# power.net
KiCad netlist of a schematic drawn in Altium Designer
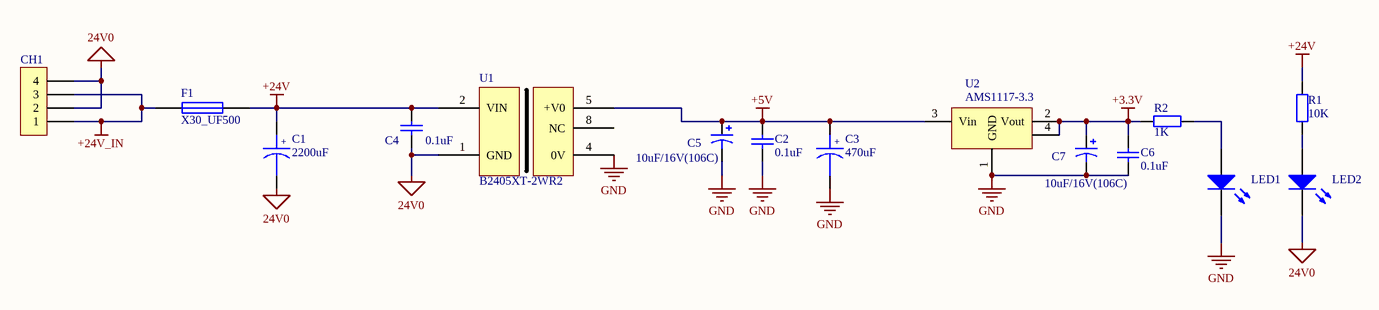
[diagram p0: power.SchDoc]

(export (version "E")
  (design (tool "Eeschema 10.0.6"))
  (components
    (comp (ref "C1")
      (value "C_2200uF")
      (footprint "C7.8*17")
      (fields (field (name "ALTIUM_UNNAMED_1") "2200uF"))
      (libsource (lib "myIntegrated_Library1") (part "C_2200uF"))
    )
    (comp (ref "C2")
      (value "0.1uF")
      (footprint "0805")
      (description "Capacitor")
      (fields (field (name "Comment") "Cap") (field (name "PUBLISHER") "Altium Limited"))
      (libsource (lib "Miscellaneous Devices") (part "Cap"))
    )
    (comp (ref "C3")
      (value "C_2200uF")
      (footprint "C5*10")
      (fields (field (name "ALTIUM_UNNAMED_1") "470uF"))
      (libsource (lib "myIntegrated_Library1") (part "C_2200uF"))
    )
    (comp (ref "C4")
      (value "0.1uF")
      (footprint "0805")
      (description "Capacitor")
      (fields (field (name "Comment") "Cap") (field (name "PUBLISHER") "Altium Limited"))
      (libsource (lib "Miscellaneous Devices") (part "Cap"))
    )
    (comp (ref "C5")
      (value "10uF/16V(106C)")
      (footprint "CAP A-3216")
      (description "Polarized Capacitor (Surface Mount)")
      (fields (field (name "Comment") "Cap Pol3") (field (name "PUBLISHER") "Altium Limited"))
      (libsource (lib "Miscellaneous Devices") (part "Cap Pol3"))
    )
    (comp (ref "C6")
      (value "0.1uF")
      (footprint "0805")
      (description "Capacitor")
      (fields (field (name "Comment") "Cap") (field (name "PUBLISHER") "Altium Limited"))
      (libsource (lib "Miscellaneous Devices") (part "Cap"))
    )
    (comp (ref "C7")
      (value "10uF/16V(106C)")
      (footprint "CAP A-3216")
      (description "Polarized Capacitor (Surface Mount)")
      (fields (field (name "Comment") "Cap Pol3") (field (name "PUBLISHER") "Altium Limited"))
      (libsource (lib "Miscellaneous Devices") (part "Cap Pol3"))
    )
    (comp (ref "CH1")
      (value "HEADER1X4")
      (footprint "CH3.96-4PIN")
      (libsource (lib "myIntegrated_Library1") (part "HEADER1X4"))
    )
    (comp (ref "F1")
      (value "X30_UF500")
      (footprint "X30UF600")
      (description "Fuse")
      (fields (field (name "PUBLISHER") "Altium Limited"))
      (libsource (lib "Miscellaneous Devices") (part "Fuse 1"))
    )
    (comp (ref "LED1")
      (value "~")
      (footprint "LED-0805")
      (description "Typical RED, GREEN, YELLOW, AMBER GaAs LED")
      (fields (field (name "PUBLISHER") "Altium Limited"))
      (libsource (lib "Miscellaneous Devices") (part "LED2"))
    )
    (comp (ref "LED2")
      (value "~")
      (footprint "LED-0805")
      (description "Typical RED, GREEN, YELLOW, AMBER GaAs LED")
      (fields (field (name "PUBLISHER") "Altium Limited"))
      (libsource (lib "Miscellaneous Devices") (part "LED2"))
    )
    (comp (ref "R1")
      (value "10K")
      (footprint "0805")
      (description "Resistor")
      (fields (field (name "Comment") "Res2") (field (name "PUBLISHER") "Altium Limited"))
      (libsource (lib "Miscellaneous Devices") (part "Res2"))
    )
    (comp (ref "R2")
      (value "1K")
      (footprint "0805")
      (description "Resistor")
      (fields (field (name "Comment") "Res2") (field (name "PUBLISHER") "Altium Limited"))
      (libsource (lib "") (part "Res2_1"))
    )
    (comp (ref "U1")
      (value "B2405XT-2WR2")
      (footprint "B2405XT-2WR2")
      (libsource (lib "myIntegrated_Library1") (part "B2405XT-2WR2"))
    )
    (comp (ref "U2")
      (value "AMS1117-3.3")
      (footprint "SOT223")
      (libsource (lib "货架电子标签元件库") (part "AMS1117-5"))
    )
  )
  (nets
    (net (code "1") (name "+3.3V") (class "Default")
      (node (ref "C6") (pin "2") (pinfunction "2_2") (pintype "passive"))
      (node (ref "C7") (pin "1") (pinfunction "1_1") (pintype "passive"))
      (node (ref "R2") (pin "2") (pinfunction "2_2") (pintype "passive"))
      (node (ref "U2") (pin "2") (pinfunction "Vout_2") (pintype "passive"))
      (node (ref "U2") (pin "4") (pintype "passive"))
    )
    (net (code "2") (name "+5V") (class "Default")
      (node (ref "C2") (pin "2") (pinfunction "2_2") (pintype "passive"))
      (node (ref "C3") (pin "1") (pinfunction "1_1") (pintype "passive"))
      (node (ref "C5") (pin "1") (pinfunction "1_1") (pintype "passive"))
      (node (ref "U1") (pin "5") (pinfunction "+V0_5") (pintype "passive"))
      (node (ref "U2") (pin "3") (pinfunction "Vin_3") (pintype "passive"))
    )
    (net (code "3") (name "+24V") (class "Default")
      (node (ref "C1") (pin "1") (pinfunction "1_1") (pintype "passive"))
      (node (ref "C4") (pin "2") (pinfunction "2_2") (pintype "passive"))
      (node (ref "F1") (pin "2") (pinfunction "2_2") (pintype "passive"))
      (node (ref "R1") (pin "2") (pinfunction "2_2") (pintype "passive"))
      (node (ref "U1") (pin "2") (pinfunction "VIN_2") (pintype "passive"))
    )
    (net (code "4") (name "+24V_IN") (class "Default")
      (node (ref "CH1") (pin "1") (pinfunction "1_1") (pintype "passive"))
      (node (ref "CH1") (pin "3") (pinfunction "3_3") (pintype "passive"))
      (node (ref "F1") (pin "1") (pinfunction "1_1") (pintype "passive"))
    )
    (net (code "5") (name "24V0") (class "Default")
      (node (ref "C1") (pin "2") (pinfunction "2_2") (pintype "passive"))
      (node (ref "C4") (pin "1") (pinfunction "1_1") (pintype "passive"))
      (node (ref "CH1") (pin "2") (pinfunction "2_2") (pintype "passive"))
      (node (ref "CH1") (pin "4") (pinfunction "4_4") (pintype "passive"))
      (node (ref "LED2") (pin "2") (pinfunction "K_2") (pintype "passive"))
      (node (ref "U1") (pin "1") (pinfunction "GND_1") (pintype "passive"))
    )
    (net (code "6") (name "GND") (class "Default")
      (node (ref "C2") (pin "1") (pinfunction "1_1") (pintype "passive"))
      (node (ref "C3") (pin "2") (pinfunction "2_2") (pintype "passive"))
      (node (ref "C5") (pin "2") (pinfunction "2_2") (pintype "passive"))
      (node (ref "C6") (pin "1") (pinfunction "1_1") (pintype "passive"))
      (node (ref "C7") (pin "2") (pinfunction "2_2") (pintype "passive"))
      (node (ref "LED1") (pin "2") (pinfunction "K_2") (pintype "passive"))
      (node (ref "U1") (pin "4") (pinfunction "0V_4") (pintype "passive"))
      (node (ref "U2") (pin "1") (pinfunction "GND_1") (pintype "passive"))
    )
    (net (code "7") (name "Net-(LED1-A)") (class "Default")
      (node (ref "LED1") (pin "1") (pinfunction "A_1") (pintype "passive"))
      (node (ref "R2") (pin "1") (pinfunction "1_1") (pintype "passive"))
    )
    (net (code "8") (name "Net-(LED2-A)") (class "Default")
      (node (ref "LED2") (pin "1") (pinfunction "A_1") (pintype "passive"))
      (node (ref "R1") (pin "1") (pinfunction "1_1") (pintype "passive"))
    )
    (net (code "9") (name "unconnected-(U1-NC-Pad8)") (class "Default")
      (node (ref "U1") (pin "8") (pinfunction "NC_8") (pintype "passive"))
    )
  )
)
